# 6_pin_plank.net
KiCad netlist of a schematic drawn in EAGLE
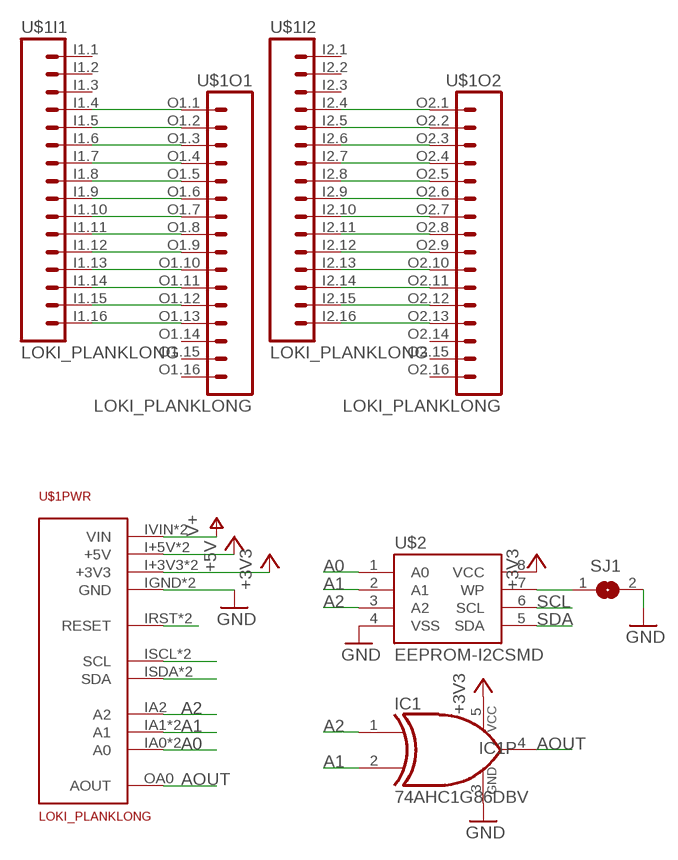
[diagram p0: schematic, sheet 1]

(export (version "E")
  (design (tool "Eeschema 10.0.6"))
  (components
    (comp (ref "IC1")
      (value "74AHC1G86DBV")
      (footprint "eagle-import:SOT23-5")
      (libsource (lib "eagle-import") (part "741G86DBVAHC"))
    )
    (comp (ref "SJ1") (value "SJ") (footprint "eagle-import:SJ") (libsource (lib "eagle-import") (part "SJ")))
    (comp (ref "U$1")
      (value "LOKI_PLANKLONG")
      (footprint "eagle-import:PLANK_LONG")
      (libsource (lib "eagle-import") (part "LOKI_PLANKLONG"))
    )
    (comp (ref "U$2")
      (value "EEPROM-I2CSMD")
      (footprint "eagle-import:SO08")
      (libsource (lib "eagle-import") (part "EEPROM-I2CSMD"))
    )
  )
  (nets
    (net (code "1") (name "+3V3") (class "Default")
      (node (ref "IC1") (pin "5") (pinfunction "VCC_5") (pintype "power_in"))
      (node (ref "U$1") (pin "I+3V3") (pinfunction "+3V3_I+3V3") (pintype "power_in"))
      (node (ref "U$1") (pin "O+3V3") (pinfunction "+3V3_O+3V3") (pintype "power_in"))
      (node (ref "U$2") (pin "8") (pinfunction "VCC_8") (pintype "power_in"))
    )
    (net (code "2") (name "+5V") (class "Default")
      (node (ref "U$1") (pin "I+5V") (pinfunction "+5V_I+5V") (pintype "power_in"))
      (node (ref "U$1") (pin "O+5V") (pinfunction "+5V_O+5V") (pintype "power_in"))
    )
    (net (code "3") (name "/A0") (class "Default")
      (node (ref "U$1") (pin "IA0") (pinfunction "A0_IA0") (pintype "output"))
      (node (ref "U$1") (pin "OA1") (pinfunction "A0_OA1") (pintype "output"))
      (node (ref "U$2") (pin "1") (pinfunction "A0_1") (pintype "bidirectional"))
    )
    (net (code "4") (name "/A1") (class "Default")
      (node (ref "IC1") (pin "2") (pinfunction "I1_2") (pintype "input"))
      (node (ref "U$1") (pin "IA1") (pinfunction "A1_IA1") (pintype "output"))
      (node (ref "U$1") (pin "OA2") (pinfunction "A1_OA2") (pintype "output"))
      (node (ref "U$2") (pin "2") (pinfunction "A1_2") (pintype "bidirectional"))
    )
    (net (code "5") (name "/A2") (class "Default")
      (node (ref "IC1") (pin "1") (pinfunction "I0_1") (pintype "input"))
      (node (ref "U$1") (pin "IA2") (pinfunction "A2_IA2") (pintype "output"))
      (node (ref "U$2") (pin "3") (pinfunction "A2_3") (pintype "bidirectional"))
    )
    (net (code "6") (name "/AOUT") (class "Default")
      (node (ref "IC1") (pin "4") (pinfunction "O_4") (pintype "output"))
      (node (ref "U$1") (pin "OA0") (pinfunction "AOUT_OA0") (pintype "input"))
    )
    (net (code "7") (name "/SCL") (class "Default")
      (node (ref "U$1") (pin "ISCL") (pinfunction "SCL_ISCL") (pintype "bidirectional"))
      (node (ref "U$1") (pin "OSCL") (pinfunction "SCL_OSCL") (pintype "bidirectional"))
      (node (ref "U$2") (pin "6") (pinfunction "SCL_6") (pintype "bidirectional"))
    )
    (net (code "8") (name "/SDA") (class "Default")
      (node (ref "U$1") (pin "ISDA") (pinfunction "SDA_ISDA") (pintype "bidirectional"))
      (node (ref "U$1") (pin "OSDA") (pinfunction "SDA_OSDA") (pintype "bidirectional"))
      (node (ref "U$2") (pin "5") (pinfunction "SDA_5") (pintype "bidirectional"))
    )
    (net (code "9") (name "GND") (class "Default")
      (node (ref "IC1") (pin "3") (pinfunction "GND_3") (pintype "power_in"))
      (node (ref "SJ1") (pin "2") (pinfunction "2_2") (pintype "passive"))
      (node (ref "U$1") (pin "IGND") (pinfunction "GND_IGND") (pintype "power_in"))
      (node (ref "U$1") (pin "OGND") (pinfunction "GND_OGND") (pintype "power_in"))
      (node (ref "U$2") (pin "4") (pinfunction "VSS_4") (pintype "power_in"))
    )
    (net (code "10") (name "Net-(U$1A-4)") (class "Default")
      (node (ref "U$1") (pin "I1.4") (pinfunction "4_I1.4") (pintype "passive"))
      (node (ref "U$1") (pin "O1.1") (pinfunction "1_O1.1") (pintype "passive"))
    )
    (net (code "11") (name "Net-(U$1A-5)") (class "Default")
      (node (ref "U$1") (pin "I1.5") (pinfunction "5_I1.5") (pintype "passive"))
      (node (ref "U$1") (pin "O1.2") (pinfunction "2_O1.2") (pintype "passive"))
    )
    (net (code "12") (name "Net-(U$1A-6)") (class "Default")
      (node (ref "U$1") (pin "I1.6") (pinfunction "6_I1.6") (pintype "passive"))
      (node (ref "U$1") (pin "O1.3") (pinfunction "3_O1.3") (pintype "passive"))
    )
    (net (code "13") (name "Net-(U$1A-7)") (class "Default")
      (node (ref "U$1") (pin "I1.7") (pinfunction "7_I1.7") (pintype "passive"))
      (node (ref "U$1") (pin "O1.4") (pinfunction "4_O1.4") (pintype "passive"))
    )
    (net (code "14") (name "Net-(U$1A-8)") (class "Default")
      (node (ref "U$1") (pin "I1.8") (pinfunction "8_I1.8") (pintype "passive"))
      (node (ref "U$1") (pin "O1.5") (pinfunction "5_O1.5") (pintype "passive"))
    )
    (net (code "15") (name "Net-(U$1A-9)") (class "Default")
      (node (ref "U$1") (pin "I1.9") (pinfunction "9_I1.9") (pintype "passive"))
      (node (ref "U$1") (pin "O1.6") (pinfunction "6_O1.6") (pintype "passive"))
    )
    (net (code "16") (name "Net-(U$1A-10)") (class "Default")
      (node (ref "U$1") (pin "I1.10") (pinfunction "10_I1.10") (pintype "passive"))
      (node (ref "U$1") (pin "O1.7") (pinfunction "7_O1.7") (pintype "passive"))
    )
    (net (code "17") (name "Net-(U$1A-11)") (class "Default")
      (node (ref "U$1") (pin "I1.11") (pinfunction "11_I1.11") (pintype "passive"))
      (node (ref "U$1") (pin "O1.8") (pinfunction "8_O1.8") (pintype "passive"))
    )
    (net (code "18") (name "Net-(U$1A-12)") (class "Default")
      (node (ref "U$1") (pin "I1.12") (pinfunction "12_I1.12") (pintype "passive"))
      (node (ref "U$1") (pin "O1.9") (pinfunction "9_O1.9") (pintype "passive"))
    )
    (net (code "19") (name "Net-(U$1A-13)") (class "Default")
      (node (ref "U$1") (pin "I1.13") (pinfunction "13_I1.13") (pintype "passive"))
      (node (ref "U$1") (pin "O1.10") (pinfunction "10_O1.10") (pintype "passive"))
    )
    (net (code "20") (name "Net-(U$1A-14)") (class "Default")
      (node (ref "U$1") (pin "I1.14") (pinfunction "14_I1.14") (pintype "passive"))
      (node (ref "U$1") (pin "O1.11") (pinfunction "11_O1.11") (pintype "passive"))
    )
    (net (code "21") (name "Net-(U$1A-15)") (class "Default")
      (node (ref "U$1") (pin "I1.15") (pinfunction "15_I1.15") (pintype "passive"))
      (node (ref "U$1") (pin "O1.12") (pinfunction "12_O1.12") (pintype "passive"))
    )
    (net (code "22") (name "Net-(U$1A-16)") (class "Default")
      (node (ref "U$1") (pin "I1.16") (pinfunction "16_I1.16") (pintype "passive"))
      (node (ref "U$1") (pin "O1.13") (pinfunction "13_O1.13") (pintype "passive"))
    )
    (net (code "23") (name "Net-(U$1B-4)") (class "Default")
      (node (ref "U$1") (pin "I2.4") (pinfunction "4_I2.4") (pintype "passive"))
      (node (ref "U$1") (pin "O2.1") (pinfunction "1_O2.1") (pintype "passive"))
    )
    (net (code "24") (name "Net-(U$1B-5)") (class "Default")
      (node (ref "U$1") (pin "I2.5") (pinfunction "5_I2.5") (pintype "passive"))
      (node (ref "U$1") (pin "O2.2") (pinfunction "2_O2.2") (pintype "passive"))
    )
    (net (code "25") (name "Net-(U$1B-6)") (class "Default")
      (node (ref "U$1") (pin "I2.6") (pinfunction "6_I2.6") (pintype "passive"))
      (node (ref "U$1") (pin "O2.3") (pinfunction "3_O2.3") (pintype "passive"))
    )
    (net (code "26") (name "Net-(U$1B-7)") (class "Default")
      (node (ref "U$1") (pin "I2.7") (pinfunction "7_I2.7") (pintype "passive"))
      (node (ref "U$1") (pin "O2.4") (pinfunction "4_O2.4") (pintype "passive"))
    )
    (net (code "27") (name "Net-(U$1B-8)") (class "Default")
      (node (ref "U$1") (pin "I2.8") (pinfunction "8_I2.8") (pintype "passive"))
      (node (ref "U$1") (pin "O2.5") (pinfunction "5_O2.5") (pintype "passive"))
    )
    (net (code "28") (name "Net-(U$1B-9)") (class "Default")
      (node (ref "U$1") (pin "I2.9") (pinfunction "9_I2.9") (pintype "passive"))
      (node (ref "U$1") (pin "O2.6") (pinfunction "6_O2.6") (pintype "passive"))
    )
    (net (code "29") (name "Net-(U$1B-10)") (class "Default")
      (node (ref "U$1") (pin "I2.10") (pinfunction "10_I2.10") (pintype "passive"))
      (node (ref "U$1") (pin "O2.7") (pinfunction "7_O2.7") (pintype "passive"))
    )
    (net (code "30") (name "Net-(U$1B-11)") (class "Default")
      (node (ref "U$1") (pin "I2.11") (pinfunction "11_I2.11") (pintype "passive"))
      (node (ref "U$1") (pin "O2.8") (pinfunction "8_O2.8") (pintype "passive"))
    )
    (net (code "31") (name "Net-(U$1B-12)") (class "Default")
      (node (ref "U$1") (pin "I2.12") (pinfunction "12_I2.12") (pintype "passive"))
      (node (ref "U$1") (pin "O2.9") (pinfunction "9_O2.9") (pintype "passive"))
    )
    (net (code "32") (name "Net-(U$1B-13)") (class "Default")
      (node (ref "U$1") (pin "I2.13") (pinfunction "13_I2.13") (pintype "passive"))
      (node (ref "U$1") (pin "O2.10") (pinfunction "10_O2.10") (pintype "passive"))
    )
    (net (code "33") (name "Net-(U$1B-14)") (class "Default")
      (node (ref "U$1") (pin "I2.14") (pinfunction "14_I2.14") (pintype "passive"))
      (node (ref "U$1") (pin "O2.11") (pinfunction "11_O2.11") (pintype "passive"))
    )
    (net (code "34") (name "Net-(U$1B-15)") (class "Default")
      (node (ref "U$1") (pin "I2.15") (pinfunction "15_I2.15") (pintype "passive"))
      (node (ref "U$1") (pin "O2.12") (pinfunction "12_O2.12") (pintype "passive"))
    )
    (net (code "35") (name "Net-(U$1B-16)") (class "Default")
      (node (ref "U$1") (pin "I2.16") (pinfunction "16_I2.16") (pintype "passive"))
      (node (ref "U$1") (pin "O2.13") (pinfunction "13_O2.13") (pintype "passive"))
    )
    (net (code "36") (name "Net-(U$1E-RESET-PadIRST)") (class "Default")
      (node (ref "U$1") (pin "IRST") (pinfunction "RESET_IRST") (pintype "input"))
      (node (ref "U$1") (pin "ORST") (pinfunction "RESET_ORST") (pintype "input"))
    )
    (net (code "37") (name "Net-(U$2-WP)") (class "Default")
      (node (ref "SJ1") (pin "1") (pinfunction "1_1") (pintype "passive"))
      (node (ref "U$2") (pin "7") (pinfunction "WP_7") (pintype "bidirectional"))
    )
    (net (code "38") (name "V+") (class "Default")
      (node (ref "U$1") (pin "IVIN") (pinfunction "VIN_IVIN") (pintype "power_in"))
      (node (ref "U$1") (pin "OVIN") (pinfunction "VIN_OVIN") (pintype "power_in"))
    )
    (net (code "39") (name "unconnected-(U$1A-1-PadI1.1)") (class "Default")
      (node (ref "U$1") (pin "I1.1") (pinfunction "1_I1.1") (pintype "passive"))
    )
    (net (code "40") (name "unconnected-(U$1A-2-PadI1.2)") (class "Default")
      (node (ref "U$1") (pin "I1.2") (pinfunction "2_I1.2") (pintype "passive"))
    )
    (net (code "41") (name "unconnected-(U$1A-3-PadI1.3)") (class "Default")
      (node (ref "U$1") (pin "I1.3") (pinfunction "3_I1.3") (pintype "passive"))
    )
    (net (code "42") (name "unconnected-(U$1B-1-PadI2.1)") (class "Default")
      (node (ref "U$1") (pin "I2.1") (pinfunction "1_I2.1") (pintype "passive"))
    )
    (net (code "43") (name "unconnected-(U$1B-2-PadI2.2)") (class "Default")
      (node (ref "U$1") (pin "I2.2") (pinfunction "2_I2.2") (pintype "passive"))
    )
    (net (code "44") (name "unconnected-(U$1B-3-PadI2.3)") (class "Default")
      (node (ref "U$1") (pin "I2.3") (pinfunction "3_I2.3") (pintype "passive"))
    )
    (net (code "45") (name "unconnected-(U$1C-14-PadO1.14)") (class "Default")
      (node (ref "U$1") (pin "O1.14") (pinfunction "14_O1.14") (pintype "passive"))
    )
    (net (code "46") (name "unconnected-(U$1C-15-PadO1.15)") (class "Default")
      (node (ref "U$1") (pin "O1.15") (pinfunction "15_O1.15") (pintype "passive"))
    )
    (net (code "47") (name "unconnected-(U$1C-16-PadO1.16)") (class "Default")
      (node (ref "U$1") (pin "O1.16") (pinfunction "16_O1.16") (pintype "passive"))
    )
    (net (code "48") (name "unconnected-(U$1D-14-PadO2.14)") (class "Default")
      (node (ref "U$1") (pin "O2.14") (pinfunction "14_O2.14") (pintype "passive"))
    )
    (net (code "49") (name "unconnected-(U$1D-15-PadO2.15)") (class "Default")
      (node (ref "U$1") (pin "O2.15") (pinfunction "15_O2.15") (pintype "passive"))
    )
    (net (code "50") (name "unconnected-(U$1D-16-PadO2.16)") (class "Default")
      (node (ref "U$1") (pin "O2.16") (pinfunction "16_O2.16") (pintype "passive"))
    )
  )
)
